# TPS60403.net
KiCad netlist of a schematic drawn in Altium Designer
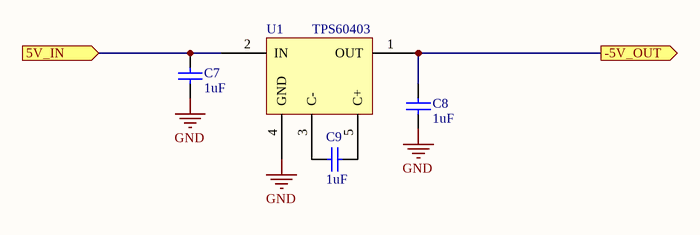
[diagram p0: TPS60403.SchDoc]

(export (version "E")
  (design (tool "Eeschema 10.0.6"))
  (components
    (comp (ref "C7")
      (value "1uF")
      (footprint "CAP_0603")
      (description "Capacitor (Semiconductor SIM Model)")
      (fields (field (name "PUBLISHER") "Altium Limited"))
      (libsource (lib "Miscellaneous Devices") (part "Cap Semi"))
    )
    (comp (ref "C8")
      (value "1uF")
      (footprint "CAP_0603")
      (description "Capacitor (Semiconductor SIM Model)")
      (fields (field (name "PUBLISHER") "Altium Limited"))
      (libsource (lib "Miscellaneous Devices") (part "Cap Semi"))
    )
    (comp (ref "C9")
      (value "1uF")
      (footprint "CAP_0603")
      (description "Capacitor (Semiconductor SIM Model)")
      (fields (field (name "PUBLISHER") "Altium Limited"))
      (libsource (lib "Miscellaneous Devices") (part "Cap Semi"))
    )
    (comp (ref "U1")
      (value "TPS60403")
      (footprint "SOT23-5")
      (libsource (lib "TPS60403") (part "Component_1"))
    )
  )
  (nets
    (net (code "1") (name "/-5V_OUT") (class "Default")
      (node (ref "C8") (pin "1") (pinfunction "1_1") (pintype "passive"))
      (node (ref "U1") (pin "1") (pinfunction "OUT_1") (pintype "passive"))
    )
    (net (code "2") (name "/5V_IN") (class "Default")
      (node (ref "C7") (pin "1") (pinfunction "1_1") (pintype "passive"))
      (node (ref "U1") (pin "2") (pinfunction "IN_2") (pintype "passive"))
    )
    (net (code "3") (name "GND") (class "Default")
      (node (ref "C7") (pin "2") (pinfunction "2_2") (pintype "passive"))
      (node (ref "C8") (pin "2") (pinfunction "2_2") (pintype "passive"))
      (node (ref "U1") (pin "4") (pinfunction "GND_4") (pintype "passive"))
    )
    (net (code "4") (name "Net-(U1-C+)") (class "Default")
      (node (ref "C9") (pin "1") (pinfunction "1_1") (pintype "passive"))
      (node (ref "U1") (pin "5") (pinfunction "C+_5") (pintype "passive"))
    )
    (net (code "5") (name "Net-(U1-C-)") (class "Default")
      (node (ref "C9") (pin "2") (pinfunction "2_2") (pintype "passive"))
      (node (ref "U1") (pin "3") (pinfunction "C-_3") (pintype "passive"))
    )
  )
)
